# MAIN.net
KiCad netlist of a schematic drawn in Altium Designer
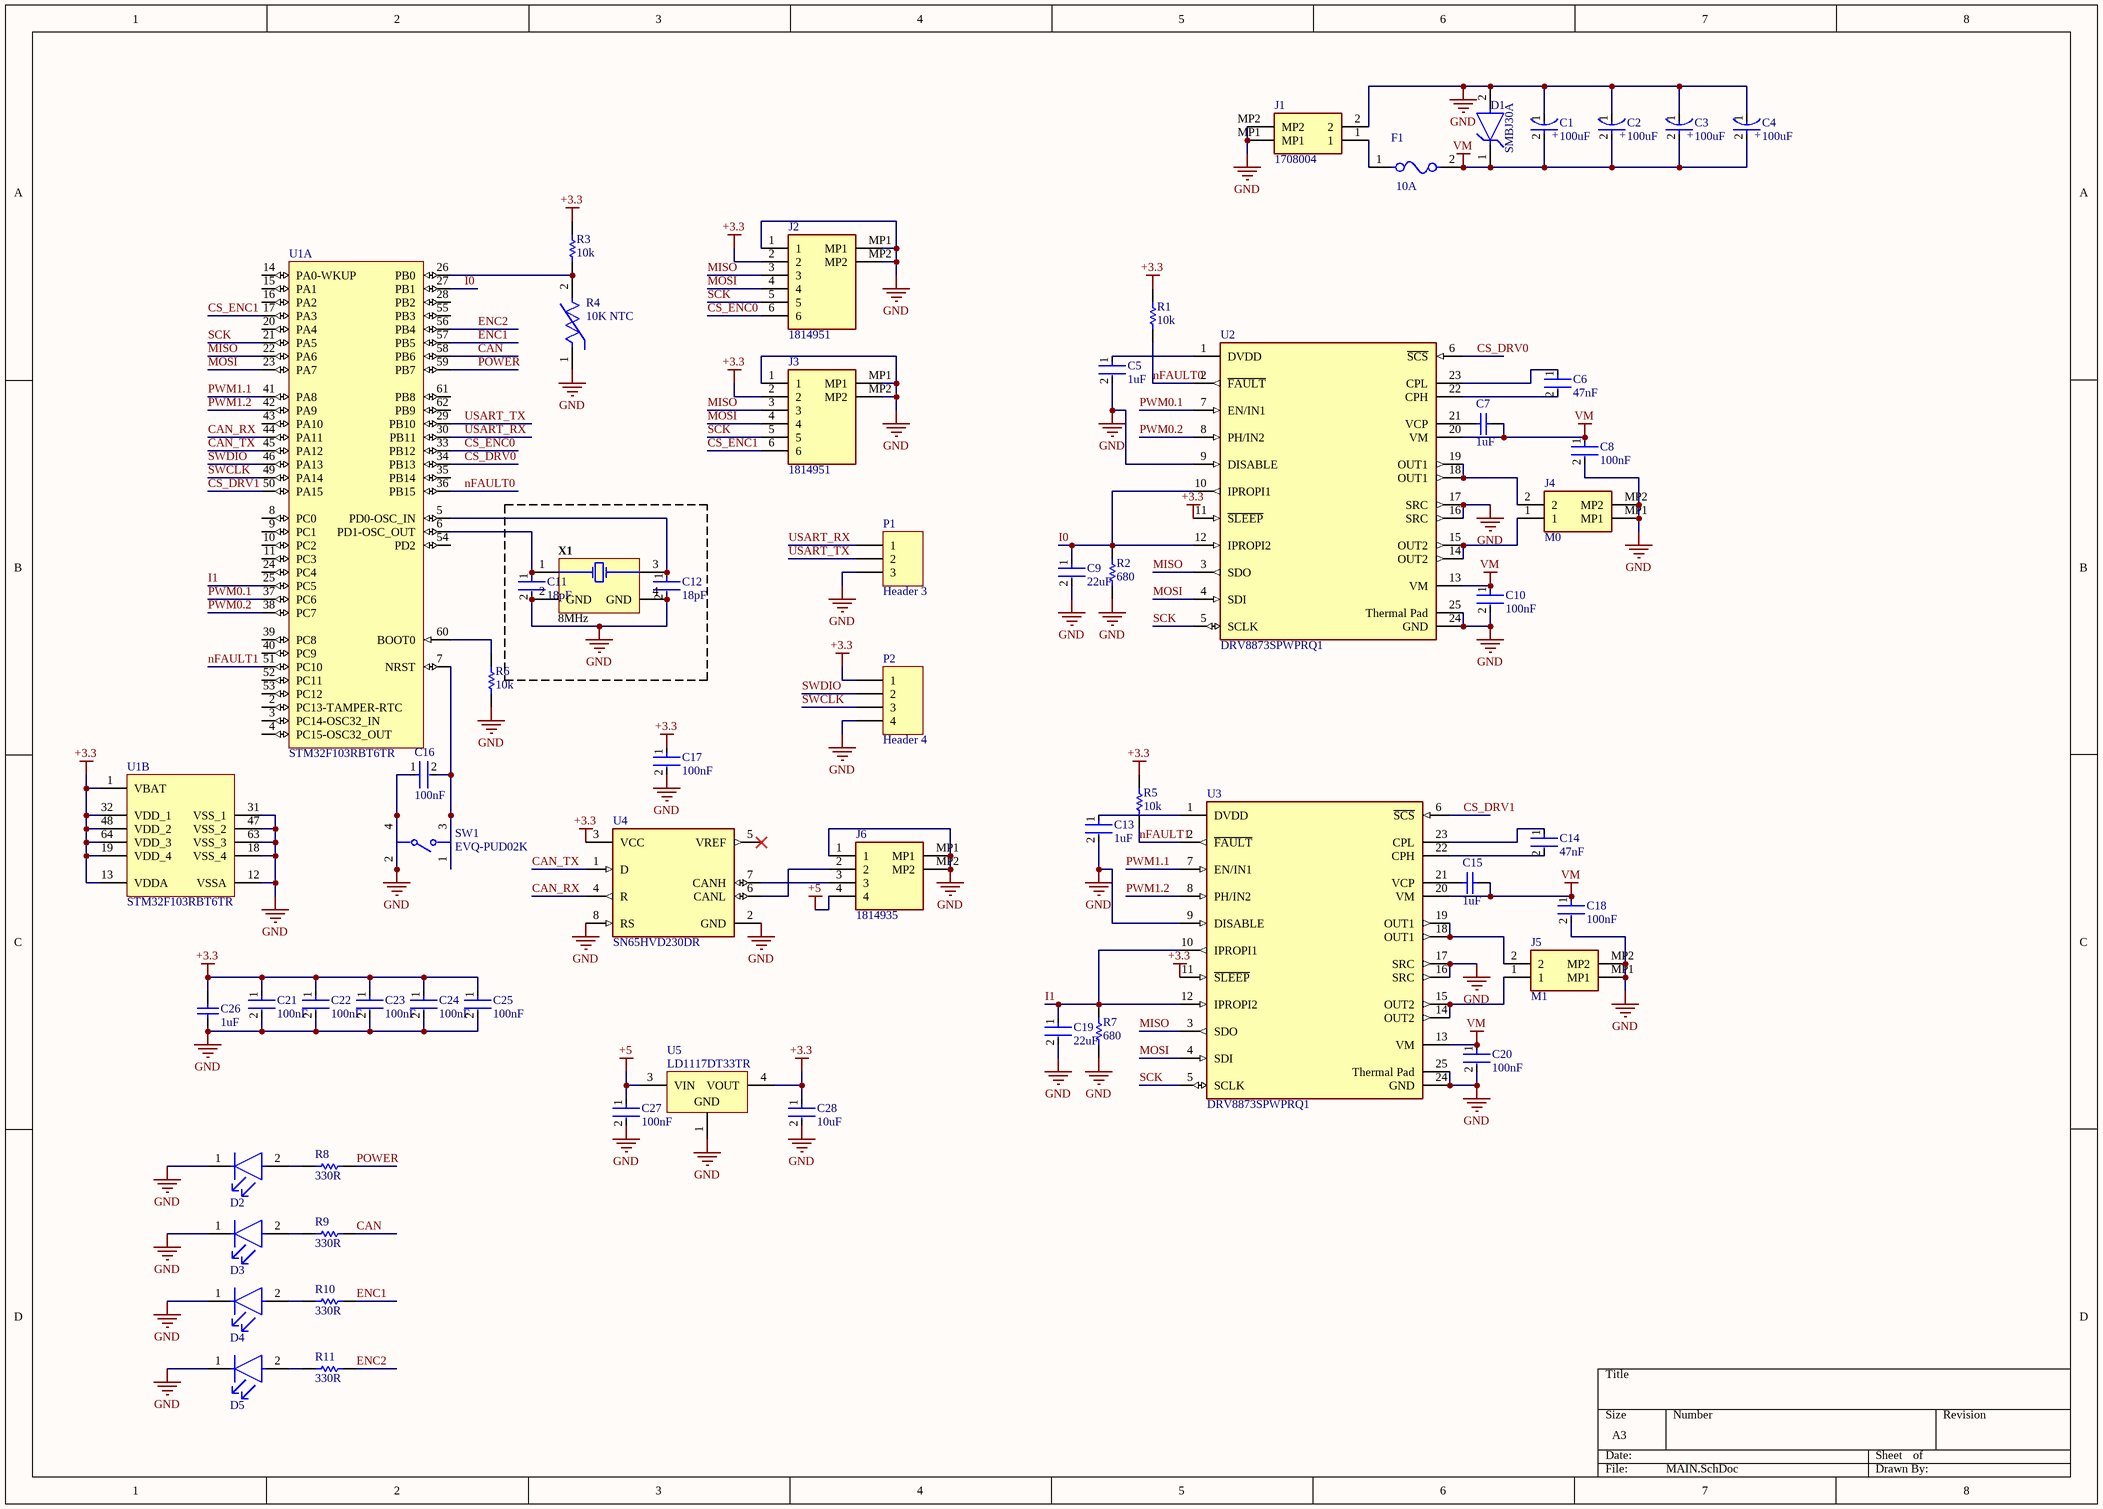
[diagram p0: MAIN.SchDoc]

(export (version "E")
  (design (tool "Eeschema 10.0.6"))
  (components
    (comp (ref "C1")
      (value "100uF")
      (footprint "FP-FTD-MFG")
      (description "CAP ALUM 100UF 20% 35V SMD")
      (fields (field (name "VOLTAGE") "35V") (field (name "TOLERANCE") "20%"))
      (libsource (lib "Altium Content Vault") (part "a00bbbee19879c290e62620ae7e47b1"))
    )
    (comp (ref "C2")
      (value "100uF")
      (footprint "FP-FTD-MFG")
      (description "CAP ALUM 100UF 20% 35V SMD")
      (fields (field (name "VOLTAGE") "35V") (field (name "TOLERANCE") "20%"))
      (libsource (lib "Altium Content Vault") (part "a00bbbee19879c290e62620ae7e47b1"))
    )
    (comp (ref "C3")
      (value "100uF")
      (footprint "FP-FTD-MFG")
      (description "CAP ALUM 100UF 20% 35V SMD")
      (fields (field (name "VOLTAGE") "35V") (field (name "TOLERANCE") "20%"))
      (libsource (lib "Altium Content Vault") (part "a00bbbee19879c290e62620ae7e47b1"))
    )
    (comp (ref "C4")
      (value "100uF")
      (footprint "FP-FTD-MFG")
      (description "CAP ALUM 100UF 20% 35V SMD")
      (fields (field (name "VOLTAGE") "35V") (field (name "TOLERANCE") "20%"))
      (libsource (lib "Altium Content Vault") (part "a00bbbee19879c290e62620ae7e47b1"))
    )
    (comp (ref "C5")
      (value "1uF")
      (footprint "FP-0805-L_2_01_0_2-W_1_25-IPC_B")
      (description "General Purpose Ceramic Capacitor, 0805, 100nF, 10%, X7R, 15%, 100V")
      (fields (field (name "VOLTAGE") "100V") (field (name "TOLERANCE") "10%"))
      (libsource (lib "Altium Content Vault") (part "b4654b650e69147ec39a6b967a45e02"))
    )
    (comp (ref "C6")
      (value "47nF")
      (footprint "FP-C0805C-DN-IPC_A")
      (description "CAP CER 0.047UF 50V X7R 0805")
      (fields
        (field (name "MANUFACTURER PART NUMBER") "C0805C473K5RACTU")
        (field (name "OCTOPART") "https://octopart.com/c0805c473k5ractu-kemet-138387")
      )
      (libsource (lib "Altium Content Vault") (part "b4654b650e69147ec39a6b967a45e02"))
    )
    (comp (ref "C7")
      (value "1uF")
      (footprint "CAPC2013X145X50ML20T25")
      (fields (field (name "MANUFACTURER") "Kemet") (field (name "PART NUMBER") "C0805C105K4PACTU"))
      (libsource (lib "Altium Content Vault") (part "CAP"))
    )
    (comp (ref "C8")
      (value "100nF")
      (footprint "FP-0805-L_2_01_0_2-W_1_25-MFG")
      (description "General Purpose Ceramic Capacitor, 0805, 100nF, 10%, X7R, 15%, 100V")
      (fields (field (name "VOLTAGE") "100V") (field (name "TOLERANCE") "10%"))
      (libsource (lib "Altium Content Vault") (part "b4654b650e69147ec39a6b967a45e02"))
    )
    (comp (ref "C9")
      (value "22uF")
      (footprint "FP-0805-L_2_01_0_2-W_1_25-IPC_B")
      (description "General Purpose Ceramic Capacitor, 0805, 100nF, 10%, X7R, 15%, 100V")
      (fields (field (name "VOLTAGE") "100V") (field (name "TOLERANCE") "10%"))
      (libsource (lib "Altium Content Vault") (part "b4654b650e69147ec39a6b967a45e02"))
    )
    (comp (ref "C10")
      (value "100nF")
      (footprint "FP-0805-L_2_01_0_2-W_1_25-MFG")
      (description "General Purpose Ceramic Capacitor, 0805, 100nF, 10%, X7R, 15%, 100V")
      (fields (field (name "VOLTAGE") "100V") (field (name "TOLERANCE") "10%"))
      (libsource (lib "Altium Content Vault") (part "b4654b650e69147ec39a6b967a45e02"))
    )
    (comp (ref "C11")
      (value "18pF")
      (footprint "FP-C0603C-CF-MFG")
      (description "CAP CER 18PF 100V 5% NP0 0603")
      (fields (field (name "TOLERANCE") "0.05") (field (name "MANUFACTURER") "KEMET"))
      (libsource (lib "Altium Content Vault") (part "b4654b650e69147ec39a6b967a45e02"))
    )
    (comp (ref "C12")
      (value "18pF")
      (footprint "FP-C0603C-CF-MFG")
      (description "CAP CER 18PF 100V 5% NP0 0603")
      (fields (field (name "TOLERANCE") "0.05") (field (name "MANUFACTURER") "KEMET"))
      (libsource (lib "Altium Content Vault") (part "b4654b650e69147ec39a6b967a45e02"))
    )
    (comp (ref "C13")
      (value "1uF")
      (footprint "FP-0805-L_2_01_0_2-W_1_25-IPC_B")
      (description "General Purpose Ceramic Capacitor, 0805, 100nF, 10%, X7R, 15%, 100V")
      (fields (field (name "VOLTAGE") "100V") (field (name "TOLERANCE") "10%"))
      (libsource (lib "Altium Content Vault") (part "b4654b650e69147ec39a6b967a45e02"))
    )
    (comp (ref "C14")
      (value "47nF")
      (footprint "FP-C0805C-DN-IPC_A")
      (description "CAP CER 0.047UF 50V X7R 0805")
      (fields
        (field (name "MANUFACTURER PART NUMBER") "C0805C473K5RACTU")
        (field (name "OCTOPART") "https://octopart.com/c0805c473k5ractu-kemet-138387")
      )
      (libsource (lib "Altium Content Vault") (part "b4654b650e69147ec39a6b967a45e02"))
    )
    (comp (ref "C15")
      (value "1uF")
      (footprint "CAPC2013X145X50ML20T25")
      (fields (field (name "MANUFACTURER") "Kemet") (field (name "PART NUMBER") "C0805C105K4PACTU"))
      (libsource (lib "Altium Content Vault") (part "CAP"))
    )
    (comp (ref "C16")
      (value "100nF")
      (footprint "FP-0805-L_2_01_0_2-W_1_25-IPC_B")
      (description "General Purpose Ceramic Capacitor, 0805, 100nF, 10%, X7R, 15%, 100V")
      (fields (field (name "VOLTAGE") "100V") (field (name "TOLERANCE") "10%"))
      (libsource (lib "Altium Content Vault") (part "b4654b650e69147ec39a6b967a45e02"))
    )
    (comp (ref "C17")
      (value "100nF")
      (footprint "FP-0805-L_2_01_0_2-W_1_25-MFG")
      (description "General Purpose Ceramic Capacitor, 0805, 100nF, 10%, X7R, 15%, 100V")
      (fields (field (name "VOLTAGE") "100V") (field (name "TOLERANCE") "10%"))
      (libsource (lib "Altium Content Vault") (part "b4654b650e69147ec39a6b967a45e02"))
    )
    (comp (ref "C18")
      (value "100nF")
      (footprint "FP-0805-L_2_01_0_2-W_1_25-MFG")
      (description "General Purpose Ceramic Capacitor, 0805, 100nF, 10%, X7R, 15%, 100V")
      (fields (field (name "VOLTAGE") "100V") (field (name "TOLERANCE") "10%"))
      (libsource (lib "Altium Content Vault") (part "b4654b650e69147ec39a6b967a45e02"))
    )
    (comp (ref "C19")
      (value "22uF")
      (footprint "FP-0805-L_2_01_0_2-W_1_25-IPC_B")
      (description "General Purpose Ceramic Capacitor, 0805, 100nF, 10%, X7R, 15%, 100V")
      (fields (field (name "VOLTAGE") "100V") (field (name "TOLERANCE") "10%"))
      (libsource (lib "Altium Content Vault") (part "b4654b650e69147ec39a6b967a45e02"))
    )
    (comp (ref "C20")
      (value "100nF")
      (footprint "FP-0805-L_2_01_0_2-W_1_25-MFG")
      (description "General Purpose Ceramic Capacitor, 0805, 100nF, 10%, X7R, 15%, 100V")
      (fields (field (name "VOLTAGE") "100V") (field (name "TOLERANCE") "10%"))
      (libsource (lib "Altium Content Vault") (part "b4654b650e69147ec39a6b967a45e02"))
    )
    (comp (ref "C21")
      (value "100nF")
      (footprint "FP-0805-L_2_01_0_2-W_1_25-IPC_B")
      (description "General Purpose Ceramic Capacitor, 0805, 100nF, 10%, X7R, 15%, 100V")
      (fields (field (name "VOLTAGE") "100V") (field (name "TOLERANCE") "10%"))
      (libsource (lib "Altium Content Vault") (part "b4654b650e69147ec39a6b967a45e02"))
    )
    (comp (ref "C22")
      (value "100nF")
      (footprint "FP-0805-L_2_01_0_2-W_1_25-IPC_B")
      (description "General Purpose Ceramic Capacitor, 0805, 100nF, 10%, X7R, 15%, 100V")
      (fields (field (name "VOLTAGE") "100V") (field (name "TOLERANCE") "10%"))
      (libsource (lib "Altium Content Vault") (part "b4654b650e69147ec39a6b967a45e02"))
    )
    (comp (ref "C23")
      (value "100nF")
      (footprint "FP-0805-L_2_01_0_2-W_1_25-IPC_B")
      (description "General Purpose Ceramic Capacitor, 0805, 100nF, 10%, X7R, 15%, 100V")
      (fields (field (name "VOLTAGE") "100V") (field (name "TOLERANCE") "10%"))
      (libsource (lib "Altium Content Vault") (part "b4654b650e69147ec39a6b967a45e02"))
    )
    (comp (ref "C24")
      (value "100nF")
      (footprint "FP-0805-L_2_01_0_2-W_1_25-IPC_B")
      (description "General Purpose Ceramic Capacitor, 0805, 100nF, 10%, X7R, 15%, 100V")
      (fields (field (name "VOLTAGE") "100V") (field (name "TOLERANCE") "10%"))
      (libsource (lib "Altium Content Vault") (part "b4654b650e69147ec39a6b967a45e02"))
    )
    (comp (ref "C25")
      (value "100nF")
      (footprint "FP-0805-L_2_01_0_2-W_1_25-IPC_B")
      (description "General Purpose Ceramic Capacitor, 0805, 100nF, 10%, X7R, 15%, 100V")
      (fields (field (name "VOLTAGE") "100V") (field (name "TOLERANCE") "10%"))
      (libsource (lib "Altium Content Vault") (part "b4654b650e69147ec39a6b967a45e02"))
    )
    (comp (ref "C26")
      (value "1uF")
      (footprint "CAPC2013X145X50ML20T25")
      (fields (field (name "MANUFACTURER") "Kemet") (field (name "PART NUMBER") "C0805C105K4PACTU"))
      (libsource (lib "Altium Content Vault") (part "CAP"))
    )
    (comp (ref "C27")
      (value "100nF")
      (footprint "FP-0805-L_2_01_0_2-W_1_25-IPC_B")
      (description "General Purpose Ceramic Capacitor, 0805, 100nF, 10%, X7R, 15%, 100V")
      (fields (field (name "VOLTAGE") "100V") (field (name "TOLERANCE") "10%"))
      (libsource (lib "Altium Content Vault") (part "b4654b650e69147ec39a6b967a45e02"))
    )
    (comp (ref "C28")
      (value "10uF")
      (footprint "FP-C0805C-DG-IPC_B")
      (description "CAP CER 10UF 10V X5R 0805")
      (fields (field (name "TOLERANCE") "10%") (field (name "MANUFACTURER PART NUMBER") "C0805C106K8PACTU"))
      (libsource (lib "Altium Content Vault") (part "11868f565c42a9108669ba33697ecf6"))
    )
    (comp (ref "D1")
      (value "SMBJ30A")
      (footprint "FP-SMBJ30A-E3-52-0")
      (description "TVS DIODE 30VWM 48.4VC DO214AA")
      (libsource (lib "Altium Content Vault") (part "d9da4cfb8af32e832502365dfa3d88e"))
    )
    (comp (ref "D2")
      (value "TLLG4401")
      (footprint "FP-6_544-5255_01-4-MFG")
      (description "TLLG4401 LED, Green, 2mcd, 3mmDia., T-1, +/-25deg, 565nm, 7mA, 1.9V Vf, 20V Vr, 20mW, -40")
      (libsource (lib "Altium Content Vault") (part "8706943c75ba83719d021d2fdc84c58"))
    )
    (comp (ref "D3")
      (value "TLLG4401")
      (footprint "FP-6_544-5255_01-4-MFG")
      (description "TLLG4401 LED, Green, 2mcd, 3mmDia., T-1, +/-25deg, 565nm, 7mA, 1.9V Vf, 20V Vr, 20mW, -40")
      (libsource (lib "Altium Content Vault") (part "8706943c75ba83719d021d2fdc84c58"))
    )
    (comp (ref "D4")
      (value "TLLG4401")
      (footprint "FP-6_544-5255_01-4-MFG")
      (description "TLLG4401 LED, Green, 2mcd, 3mmDia., T-1, +/-25deg, 565nm, 7mA, 1.9V Vf, 20V Vr, 20mW, -40")
      (libsource (lib "Altium Content Vault") (part "8706943c75ba83719d021d2fdc84c58"))
    )
    (comp (ref "D5")
      (value "TLLG4401")
      (footprint "FP-6_544-5255_01-4-MFG")
      (description "TLLG4401 LED, Green, 2mcd, 3mmDia., T-1, +/-25deg, 565nm, 7mA, 1.9V Vf, 20V Vr, 20mW, -40")
      (libsource (lib "Altium Content Vault") (part "8706943c75ba83719d021d2fdc84c58"))
    )
    (comp (ref "F1")
      (value "10A")
      (footprint "FP-0154-MFG")
      (description "FUSE BRD MNT 4A 125VAC/VDC 2SMD")
      (fields
        (field (name "MANUFACTURER PART NUMBER") "0154004.DR")
        (field (name "MANUFACTURER") "Littelfuse")
      )
      (libsource (lib "Altium Content Vault") (part "5bcf9b9f640e542cf0359d10258e979"))
    )
    (comp (ref "J1")
      (value "1708004")
      (footprint "1708004")
      (description "Pluggable Terminal Blocks PTSM 0,5/ 2-HH- 2,5-SMD WH R32")
      (fields (field (name "MOUSER PART NUMBER") "651-1708004"))
      (libsource (lib "1708004") (part "1708004"))
    )
    (comp (ref "J2")
      (value "1814951")
      (footprint "1814951")
      (description "Pluggable Terminal Blocks PTSM 0,5/ 6-HH0-2,5- SMD WH R44")
      (libsource (lib "1814951") (part "1814951"))
    )
    (comp (ref "J3")
      (value "1814951")
      (footprint "1814951")
      (description "Pluggable Terminal Blocks PTSM 0,5/ 6-HH0-2,5- SMD WH R44")
      (libsource (lib "1814951") (part "1814951"))
    )
    (comp (ref "J4")
      (value "M0")
      (footprint "1815125")
      (description "Phoenix Contact PTSM Series, 2.5mm Pitch Printed Circuit Board Connector, 6A")
      (fields
        (field (name "MOUSER PART NUMBER") "651-1815125")
        (field (name "MANUFACTURER_PART_NUMBER") "1815125")
      )
      (libsource (lib "1815125") (part "1815125"))
    )
    (comp (ref "J5")
      (value "M1")
      (footprint "1815125")
      (description "Phoenix Contact PTSM Series, 2.5mm Pitch Printed Circuit Board Connector, 6A")
      (fields
        (field (name "MOUSER PART NUMBER") "651-1815125")
        (field (name "MANUFACTURER_PART_NUMBER") "1815125")
      )
      (libsource (lib "1815125") (part "1815125"))
    )
    (comp (ref "J6")
      (value "1814935")
      (footprint "1814935")
      (description "Pluggable Terminal Blocks PTSM 0,5/ 4-HH0-2,5- SMD WH R32")
      (libsource (lib "1814935") (part "1814935"))
    )
    (comp (ref "P1")
      (value "Header 3")
      (footprint "HDR1X3")
      (description "Header, 3-Pin")
      (fields (field (name "PUBLISHER") "Altium Limited"))
      (libsource (lib "Miscellaneous Connectors") (part "Header 3"))
    )
    (comp (ref "P2")
      (value "Header 4")
      (footprint "HDR1X4")
      (description "Header, 4-Pin")
      (fields (field (name "PUBLISHER") "Altium Limited"))
      (libsource (lib "Miscellaneous Connectors") (part "Header 4"))
    )
    (comp (ref "R1")
      (value "10k")
      (footprint "RESC2013X60X35NL10T20")
      (description "Chip Resistor, 10 KOhm, +/- 1%, 0.125 W, -55 to 155 degC, 0805 (2012 Metric), RoHS, Tape and Reel")
      (fields (field (name "MANUFACTURER") "Yageo"))
      (libsource (lib "Altium Content Vault") (part "RES-2"))
    )
    (comp (ref "R2")
      (value "680")
      (footprint "RESC2013X60X35NL10T20")
      (description "Chip Resistor, 10 KOhm, +/- 1%, 0.125 W, -55 to 155 degC, 0805 (2012 Metric), RoHS, Tape and Reel")
      (fields (field (name "MANUFACTURER") "Yageo"))
      (libsource (lib "Altium Content Vault") (part "RES-2"))
    )
    (comp (ref "R3")
      (value "10k")
      (footprint "RESC2013X60X35ML10T20")
      (fields (field (name "TOLERANCE") "5%") (field (name "MANUFACTURER") "Yageo"))
      (libsource (lib "Altium Content Vault") (part "RES-2"))
    )
    (comp (ref "R4")
      (value "10K NTC")
      (footprint "FP-NCP18-0_15-IPC_A")
      (description "NTC Thermistor for Temperature Sensor, 0603, 10kΩ, 1%, 0.1mA, 5V")
      (fields (field (name "TOLERANCE") "1%"))
      (libsource (lib "Altium Content Vault") (part "3b148a6ebabc5fb4d708a66c052d352"))
    )
    (comp (ref "R5")
      (value "10k")
      (footprint "RESC2013X60X35NL10T20")
      (description "Chip Resistor, 10 KOhm, +/- 1%, 0.125 W, -55 to 155 degC, 0805 (2012 Metric), RoHS, Tape and Reel")
      (fields (field (name "MANUFACTURER") "Yageo"))
      (libsource (lib "Altium Content Vault") (part "RES-2"))
    )
    (comp (ref "R6")
      (value "10k")
      (footprint "RESC2013X60X35ML10T20")
      (fields (field (name "TOLERANCE") "5%") (field (name "MANUFACTURER") "Yageo"))
      (libsource (lib "Altium Content Vault") (part "RES-2"))
    )
    (comp (ref "R7")
      (value "680")
      (footprint "RESC2013X60X35NL10T20")
      (description "Chip Resistor, 10 KOhm, +/- 1%, 0.125 W, -55 to 155 degC, 0805 (2012 Metric), RoHS, Tape and Reel")
      (fields (field (name "MANUFACTURER") "Yageo"))
      (libsource (lib "Altium Content Vault") (part "RES-2"))
    )
    (comp (ref "R8")
      (value "330R")
      (footprint "RESC2013X60X35ML10T20")
      (description "Chip Resistor, 1 KOhm, +/- 1%, 125 mW, -55 to 155 degC, 0805 (2012 Metric), RoHS, Tape and Reel")
      (fields (field (name "TOLERANCE") "1%") (field (name "MANUFACTURER") "Yageo"))
      (libsource (lib "Altium Content Vault") (part "RES-2"))
    )
    (comp (ref "R9")
      (value "330R")
      (footprint "RESC2013X60X35ML10T20")
      (description "Chip Resistor, 1 KOhm, +/- 1%, 125 mW, -55 to 155 degC, 0805 (2012 Metric), RoHS, Tape and Reel")
      (fields (field (name "TOLERANCE") "1%") (field (name "MANUFACTURER") "Yageo"))
      (libsource (lib "Altium Content Vault") (part "RES-2"))
    )
    (comp (ref "R10")
      (value "330R")
      (footprint "RESC2013X60X35ML10T20")
      (description "Chip Resistor, 1 KOhm, +/- 1%, 125 mW, -55 to 155 degC, 0805 (2012 Metric), RoHS, Tape and Reel")
      (fields (field (name "TOLERANCE") "1%") (field (name "MANUFACTURER") "Yageo"))
      (libsource (lib "Altium Content Vault") (part "RES-2"))
    )
    (comp (ref "R11")
      (value "330R")
      (footprint "RESC2013X60X35ML10T20")
      (description "Chip Resistor, 1 KOhm, +/- 1%, 125 mW, -55 to 155 degC, 0805 (2012 Metric), RoHS, Tape and Reel")
      (fields (field (name "TOLERANCE") "1%") (field (name "MANUFACTURER") "Yageo"))
      (libsource (lib "Altium Content Vault") (part "RES-2"))
    )
    (comp (ref "SW1")
      (value "EVQ-PUD02K")
      (footprint "FP-EVQ-PUD02K-MFG")
      (description "SWITCH TACTILE SPST-NO 0.05A 12V")
      (libsource (lib "Altium Content Vault") (part "98412ef6bd26695bde79fccaf8fa8e7"))
    )
    (comp (ref "U1")
      (value "STM32F103RBT6TR")
      (footprint "STM-LQFP64_V")
      (libsource (lib "Altium Content Vault") (part "MC-ARM-STM32F103X8_B-SQ64"))
    )
    (comp (ref "U2")
      (value "DRV8873SPWPRQ1")
      (footprint "FP-PWP0024J-MFG")
      (description "IC MTRDRV UNIPLR 0-5.5V 24HTSSOP")
      (libsource (lib "Altium Content Vault") (part "639cfc0396780f9562c68c0b1c9b09f"))
    )
    (comp (ref "U3")
      (value "DRV8873SPWPRQ1")
      (footprint "FP-PWP0024J-MFG")
      (description "IC MTRDRV UNIPLR 0-5.5V 24HTSSOP")
      (libsource (lib "Altium Content Vault") (part "639cfc0396780f9562c68c0b1c9b09f"))
    )
    (comp (ref "U4")
      (value "SN65HVD230DR")
      (footprint "FP-D0008A-IPC_A")
      (description "IC TRANSCEIVER HALF 1/1 8SOIC")
      (libsource (lib "Altium Content Vault") (part "43b56812b1adf0e60a7acfb7c27ab91"))
    )
    (comp (ref "U5")
      (value "LD1117DT33TR")
      (footprint "TO-252_M")
      (description "Fixed Low Drop Positive Voltage Regulator, 3.3V, 3-Pin DPAK, Tape and Reel")
      (libsource (lib "Altium Content Vault") (part "PM-REG-LD1117-SOT3"))
    )
    (comp (ref "X1")
      (value "8MHz")
      (footprint "TXC-7B-4_V")
      (description "SMD Seam Sealing Crystal, 8 MHz, +/- 30 ppm, 18 pF, -10 to 70 degC, 4-Pin SMD, RoHS, Tape and Reel")
      (fields (field (name "TOLERANCE") "1%"))
      (libsource (lib "Altium Content Vault") (part "XTAL-1-3-4"))
    )
  )
  (nets
    (net (code "1") (name "+3.3") (class "Default")
      (node (ref "C17") (pin "1") (pinfunction "1_1") (pintype "passive"))
      (node (ref "C21") (pin "1") (pinfunction "1_1") (pintype "passive"))
      (node (ref "C22") (pin "1") (pinfunction "1_1") (pintype "passive"))
      (node (ref "C23") (pin "1") (pinfunction "1_1") (pintype "passive"))
      (node (ref "C24") (pin "1") (pinfunction "1_1") (pintype "passive"))
      (node (ref "C25") (pin "1") (pinfunction "1_1") (pintype "passive"))
      (node (ref "C26") (pin "2") (pinfunction "2_2") (pintype "passive"))
      (node (ref "C28") (pin "1") (pinfunction "1_1") (pintype "passive"))
      (node (ref "J2") (pin "2") (pinfunction "2_2") (pintype "passive"))
      (node (ref "J3") (pin "2") (pinfunction "2_2") (pintype "passive"))
      (node (ref "P2") (pin "1") (pinfunction "1_1") (pintype "passive"))
      (node (ref "R1") (pin "2") (pinfunction "2_2") (pintype "passive"))
      (node (ref "R3") (pin "2") (pinfunction "2_2") (pintype "passive"))
      (node (ref "R5") (pin "2") (pinfunction "2_2") (pintype "passive"))
      (node (ref "U1") (pin "1") (pinfunction "VBAT_1") (pintype "power_in"))
      (node (ref "U1") (pin "13") (pinfunction "VDDA_13") (pintype "power_in"))
      (node (ref "U1") (pin "19") (pinfunction "VDD_4_19") (pintype "power_in"))
      (node (ref "U1") (pin "32") (pinfunction "VDD_1_32") (pintype "power_in"))
      (node (ref "U1") (pin "48") (pinfunction "VDD_2_48") (pintype "power_in"))
      (node (ref "U1") (pin "64") (pinfunction "VDD_3_64") (pintype "power_in"))
      (node (ref "U2") (pin "11") (pinfunction "~{SLEEP}_11") (pintype "input"))
      (node (ref "U3") (pin "11") (pinfunction "~{SLEEP}_11") (pintype "input"))
      (node (ref "U4") (pin "3") (pinfunction "VCC_3") (pintype "power_in"))
      (node (ref "U5") (pin "4") (pinfunction "VOUT_4") (pintype "power_in"))
    )
    (net (code "2") (name "+5") (class "Default")
      (node (ref "C27") (pin "1") (pinfunction "1_1") (pintype "passive"))
      (node (ref "J6") (pin "4") (pinfunction "4_4") (pintype "passive"))
      (node (ref "U5") (pin "3") (pinfunction "VIN_3") (pintype "power_in"))
    )
    (net (code "3") (name "/CAN") (class "Default")
      (node (ref "R9") (pin "1") (pinfunction "1_1") (pintype "passive"))
      (node (ref "U1") (pin "58") (pinfunction "PB6_58") (pintype "bidirectional"))
    )
    (net (code "4") (name "/CAN_RX") (class "Default")
      (node (ref "U1") (pin "44") (pinfunction "PA11_44") (pintype "bidirectional"))
      (node (ref "U4") (pin "4") (pinfunction "R_4") (pintype "output"))
    )
    (net (code "5") (name "/CAN_TX") (class "Default")
      (node (ref "U1") (pin "45") (pinfunction "PA12_45") (pintype "bidirectional"))
      (node (ref "U4") (pin "1") (pinfunction "D_1") (pintype "input"))
    )
    (net (code "6") (name "/CS_DRV0") (class "Default")
      (node (ref "U1") (pin "34") (pinfunction "PB13_34") (pintype "bidirectional"))
      (node (ref "U2") (pin "6") (pinfunction "~{SCS}_6") (pintype "input"))
    )
    (net (code "7") (name "/CS_DRV1") (class "Default")
      (node (ref "U1") (pin "50") (pinfunction "PA15_50") (pintype "bidirectional"))
      (node (ref "U3") (pin "6") (pinfunction "~{SCS}_6") (pintype "input"))
    )
    (net (code "8") (name "/CS_ENC0") (class "Default")
      (node (ref "J2") (pin "6") (pinfunction "6_6") (pintype "passive"))
      (node (ref "U1") (pin "33") (pinfunction "PB12_33") (pintype "bidirectional"))
    )
    (net (code "9") (name "/CS_ENC1") (class "Default")
      (node (ref "J3") (pin "6") (pinfunction "6_6") (pintype "passive"))
      (node (ref "U1") (pin "17") (pinfunction "PA3_17") (pintype "bidirectional"))
    )
    (net (code "10") (name "/ENC1") (class "Default")
      (node (ref "R10") (pin "1") (pinfunction "1_1") (pintype "passive"))
      (node (ref "U1") (pin "57") (pinfunction "PB5_57") (pintype "bidirectional"))
    )
    (net (code "11") (name "/ENC2") (class "Default")
      (node (ref "R11") (pin "1") (pinfunction "1_1") (pintype "passive"))
      (node (ref "U1") (pin "56") (pinfunction "PB4_56") (pintype "bidirectional"))
    )
    (net (code "12") (name "/I0") (class "Default")
      (node (ref "C9") (pin "1") (pinfunction "1_1") (pintype "passive"))
      (node (ref "R2") (pin "2") (pinfunction "2_2") (pintype "passive"))
      (node (ref "U1") (pin "27") (pinfunction "PB1_27") (pintype "bidirectional"))
      (node (ref "U2") (pin "10") (pinfunction "IPROPI1_10") (pintype "output"))
      (node (ref "U2") (pin "12") (pinfunction "IPROPI2_12") (pintype "input"))
    )
    (net (code "13") (name "/I1") (class "Default")
      (node (ref "C19") (pin "1") (pinfunction "1_1") (pintype "passive"))
      (node (ref "R7") (pin "2") (pinfunction "2_2") (pintype "passive"))
      (node (ref "U1") (pin "25") (pinfunction "PC5_25") (pintype "bidirectional"))
      (node (ref "U3") (pin "10") (pinfunction "IPROPI1_10") (pintype "output"))
      (node (ref "U3") (pin "12") (pinfunction "IPROPI2_12") (pintype "input"))
    )
    (net (code "14") (name "/MISO") (class "Default")
      (node (ref "J2") (pin "3") (pinfunction "3_3") (pintype "passive"))
      (node (ref "J3") (pin "3") (pinfunction "3_3") (pintype "passive"))
      (node (ref "U1") (pin "22") (pinfunction "PA6_22") (pintype "bidirectional"))
      (node (ref "U2") (pin "3") (pinfunction "SDO_3") (pintype "output"))
      (node (ref "U3") (pin "3") (pinfunction "SDO_3") (pintype "output"))
    )
    (net (code "15") (name "/MOSI") (class "Default")
      (node (ref "J2") (pin "4") (pinfunction "4_4") (pintype "passive"))
      (node (ref "J3") (pin "4") (pinfunction "4_4") (pintype "passive"))
      (node (ref "U1") (pin "23") (pinfunction "PA7_23") (pintype "bidirectional"))
      (node (ref "U2") (pin "4") (pinfunction "SDI_4") (pintype "input"))
      (node (ref "U3") (pin "4") (pinfunction "SDI_4") (pintype "input"))
    )
    (net (code "16") (name "/POWER") (class "Default")
      (node (ref "R8") (pin "1") (pinfunction "1_1") (pintype "passive"))
      (node (ref "U1") (pin "59") (pinfunction "PB7_59") (pintype "bidirectional"))
    )
    (net (code "17") (name "/PWM0.1") (class "Default")
      (node (ref "U1") (pin "37") (pinfunction "PC6_37") (pintype "bidirectional"))
      (node (ref "U2") (pin "7") (pinfunction "EN/IN1_7") (pintype "input"))
    )
    (net (code "18") (name "/PWM0.2") (class "Default")
      (node (ref "U1") (pin "38") (pinfunction "PC7_38") (pintype "bidirectional"))
      (node (ref "U2") (pin "8") (pinfunction "PH/IN2_8") (pintype "input"))
    )
    (net (code "19") (name "/PWM1.1") (class "Default")
      (node (ref "U1") (pin "41") (pinfunction "PA8_41") (pintype "bidirectional"))
      (node (ref "U3") (pin "7") (pinfunction "EN/IN1_7") (pintype "input"))
    )
    (net (code "20") (name "/PWM1.2") (class "Default")
      (node (ref "U1") (pin "42") (pinfunction "PA9_42") (pintype "bidirectional"))
      (node (ref "U3") (pin "8") (pinfunction "PH/IN2_8") (pintype "input"))
    )
    (net (code "21") (name "/SCK") (class "Default")
      (node (ref "J2") (pin "5") (pinfunction "5_5") (pintype "passive"))
      (node (ref "J3") (pin "5") (pinfunction "5_5") (pintype "passive"))
      (node (ref "U1") (pin "21") (pinfunction "PA5_21") (pintype "bidirectional"))
      (node (ref "U2") (pin "5") (pinfunction "SCLK_5") (pintype "bidirectional"))
      (node (ref "U3") (pin "5") (pinfunction "SCLK_5") (pintype "bidirectional"))
    )
    (net (code "22") (name "/SWCLK") (class "Default")
      (node (ref "P2") (pin "3") (pinfunction "3_3") (pintype "passive"))
      (node (ref "U1") (pin "49") (pinfunction "PA14_49") (pintype "bidirectional"))
    )
    (net (code "23") (name "/SWDIO") (class "Default")
      (node (ref "P2") (pin "2") (pinfunction "2_2") (pintype "passive"))
      (node (ref "U1") (pin "46") (pinfunction "PA13_46") (pintype "bidirectional"))
    )
    (net (code "24") (name "/USART_RX") (class "Default")
      (node (ref "P1") (pin "1") (pinfunction "1_1") (pintype "passive"))
      (node (ref "U1") (pin "30") (pinfunction "PB11_30") (pintype "bidirectional"))
    )
    (net (code "25") (name "/USART_TX") (class "Default")
      (node (ref "P1") (pin "2") (pinfunction "2_2") (pintype "passive"))
      (node (ref "U1") (pin "29") (pinfunction "PB10_29") (pintype "bidirectional"))
    )
    (net (code "26") (name "/nFAULT0") (class "Default")
      (node (ref "R1") (pin "1") (pinfunction "1_1") (pintype "passive"))
      (node (ref "U1") (pin "36") (pinfunction "PB15_36") (pintype "bidirectional"))
      (node (ref "U2") (pin "2") (pinfunction "~{FAULT}_2") (pintype "output"))
    )
    (net (code "27") (name "/nFAULT1") (class "Default")
      (node (ref "R5") (pin "1") (pinfunction "1_1") (pintype "passive"))
      (node (ref "U1") (pin "51") (pinfunction "PC10_51") (pintype "bidirectional"))
      (node (ref "U3") (pin "2") (pinfunction "~{FAULT}_2") (pintype "output"))
    )
    (net (code "28") (name "GND") (class "Default")
      (node (ref "C1") (pin "1") (pinfunction "C_1") (pintype "passive"))
      (node (ref "C10") (pin "2") (pinfunction "2_2") (pintype "passive"))
      (node (ref "C11") (pin "2") (pinfunction "2_2") (pintype "passive"))
      (node (ref "C12") (pin "2") (pinfunction "2_2") (pintype "passive"))
      (node (ref "C13") (pin "2") (pinfunction "2_2") (pintype "passive"))
      (node (ref "C16") (pin "1") (pinfunction "1_1") (pintype "passive"))
      (node (ref "C17") (pin "2") (pinfunction "2_2") (pintype "passive"))
      (node (ref "C18") (pin "2") (pinfunction "2_2") (pintype "passive"))
      (node (ref "C19") (pin "2") (pinfunction "2_2") (pintype "passive"))
      (node (ref "C2") (pin "1") (pinfunction "C_1") (pintype "passive"))
      (node (ref "C20") (pin "2") (pinfunction "2_2") (pintype "passive"))
      (node (ref "C21") (pin "2") (pinfunction "2_2") (pintype "passive"))
      (node (ref "C22") (pin "2") (pinfunction "2_2") (pintype "passive"))
      (node (ref "C23") (pin "2") (pinfunction "2_2") (pintype "passive"))
      (node (ref "C24") (pin "2") (pinfunction "2_2") (pintype "passive"))
      (node (ref "C25") (pin "2") (pinfunction "2_2") (pintype "passive"))
      (node (ref "C26") (pin "1") (pinfunction "1_1") (pintype "passive"))
      (node (ref "C27") (pin "2") (pinfunction "2_2") (pintype "passive"))
      (node (ref "C28") (pin "2") (pinfunction "2_2") (pintype "passive"))
      (node (ref "C3") (pin "1") (pinfunction "C_1") (pintype "passive"))
      (node (ref "C4") (pin "1") (pinfunction "C_1") (pintype "passive"))
      (node (ref "C5") (pin "2") (pinfunction "2_2") (pintype "passive"))
      (node (ref "C8") (pin "2") (pinfunction "2_2") (pintype "passive"))
      (node (ref "C9") (pin "2") (pinfunction "2_2") (pintype "passive"))
      (node (ref "D1") (pin "2") (pinfunction "A_2") (pintype "passive"))
      (node (ref "D2") (pin "1") (pinfunction "C_1") (pintype "passive"))
      (node (ref "D3") (pin "1") (pinfunction "C_1") (pintype "passive"))
      (node (ref "D4") (pin "1") (pinfunction "C_1") (pintype "passive"))
      (node (ref "D5") (pin "1") (pinfunction "C_1") (pintype "passive"))
      (node (ref "J1") (pin "2") (pinfunction "2_2") (pintype "passive"))
      (node (ref "J1") (pin "MP1") (pinfunction "MP1_MP1") (pintype "passive"))
      (node (ref "J1") (pin "MP2") (pinfunction "MP2_MP2") (pintype "passive"))
      (node (ref "J2") (pin "1") (pinfunction "1_1") (pintype "passive"))
      (node (ref "J2") (pin "MP1") (pinfunction "MP1_MP1") (pintype "passive"))
      (node (ref "J2") (pin "MP2") (pinfunction "MP2_MP2") (pintype "passive"))
      (node (ref "J3") (pin "1") (pinfunction "1_1") (pintype "passive"))
      (node (ref "J3") (pin "MP1") (pinfunction "MP1_MP1") (pintype "passive"))
      (node (ref "J3") (pin "MP2") (pinfunction "MP2_MP2") (pintype "passive"))
      (node (ref "J4") (pin "MP1") (pinfunction "MP1_MP1") (pintype "passive"))
      (node (ref "J4") (pin "MP2") (pinfunction "MP2_MP2") (pintype "passive"))
      (node (ref "J5") (pin "MP1") (pinfunction "MP1_MP1") (pintype "passive"))
      (node (ref "J5") (pin "MP2") (pinfunction "MP2_MP2") (pintype "passive"))
      (node (ref "J6") (pin "1") (pinfunction "1_1") (pintype "passive"))
      (node (ref "J6") (pin "MP1") (pinfunction "MP1_MP1") (pintype "passive"))
      (node (ref "J6") (pin "MP2") (pinfunction "MP2_MP2") (pintype "passive"))
      (node (ref "P1") (pin "3") (pinfunction "3_3") (pintype "passive"))
      (node (ref "P2") (pin "4") (pinfunction "4_4") (pintype "passive"))
      (node (ref "R2") (pin "1") (pinfunction "1_1") (pintype "passive"))
      (node (ref "R4") (pin "1") (pinfunction "1_1") (pintype "passive"))
      (node (ref "R6") (pin "1") (pinfunction "1_1") (pintype "passive"))
      (node (ref "R7") (pin "1") (pinfunction "1_1") (pintype "passive"))
      (node (ref "SW1") (pin "2") (pinfunction "2_2") (pintype "passive"))
      (node (ref "SW1") (pin "4") (pinfunction "4_4") (pintype "passive"))
      (node (ref "U1") (pin "12") (pinfunction "VSSA_12") (pintype "power_in"))
      (node (ref "U1") (pin "18") (pinfunction "VSS_4_18") (pintype "power_in"))
      (node (ref "U1") (pin "31") (pinfunction "VSS_1_31") (pintype "power_in"))
      (node (ref "U1") (pin "47") (pinfunction "VSS_2_47") (pintype "power_in"))
      (node (ref "U1") (pin "63") (pinfunction "VSS_3_63") (pintype "power_in"))
      (node (ref "U2") (pin "16") (pinfunction "SRC_16") (pintype "output"))
      (node (ref "U2") (pin "17") (pinfunction "SRC_17") (pintype "output"))
      (node (ref "U2") (pin "24") (pinfunction "GND_24") (pintype "power_in"))
      (node (ref "U2") (pin "25") (pinfunction "Thermal_Pad_25") (pintype "power_in"))
      (node (ref "U2") (pin "9") (pinfunction "DISABLE_9") (pintype "input"))
      (node (ref "U3") (pin "16") (pinfunction "SRC_16") (pintype "output"))
      (node (ref "U3") (pin "17") (pinfunction "SRC_17") (pintype "output"))
      (node (ref "U3") (pin "24") (pinfunction "GND_24") (pintype "power_in"))
      (node (ref "U3") (pin "25") (pinfunction "Thermal_Pad_25") (pintype "power_in"))
      (node (ref "U3") (pin "9") (pinfunction "DISABLE_9") (pintype "input"))
      (node (ref "U4") (pin "2") (pinfunction "GND_2") (pintype "power_in"))
      (node (ref "U4") (pin "8") (pinfunction "RS_8") (pintype "input"))
      (node (ref "U5") (pin "1") (pinfunction "GND_1") (pintype "power_in"))
      (node (ref "X1") (pin "2") (pinfunction "GND_2") (pintype "power_in"))
      (node (ref "X1") (pin "4") (pinfunction "GND_4") (pintype "power_in"))
    )
    (net (code "29") (name "Net-(D2-A)") (class "Default")
      (node (ref "D2") (pin "2") (pinfunction "A_2") (pintype "passive"))
      (node (ref "R8") (pin "2") (pinfunction "2_2") (pintype "passive"))
    )
    (net (code "30") (name "Net-(D3-A)") (class "Default")
      (node (ref "D3") (pin "2") (pinfunction "A_2") (pintype "passive"))
      (node (ref "R9") (pin "2") (pinfunction "2_2") (pintype "passive"))
    )
    (net (code "31") (name "Net-(D4-A)") (class "Default")
      (node (ref "D4") (pin "2") (pinfunction "A_2") (pintype "passive"))
      (node (ref "R10") (pin "2") (pinfunction "2_2") (pintype "passive"))
    )
    (net (code "32") (name "Net-(D5-A)") (class "Default")
      (node (ref "D5") (pin "2") (pinfunction "A_2") (pintype "passive"))
      (node (ref "R11") (pin "2") (pinfunction "2_2") (pintype "passive"))
    )
    (net (code "33") (name "Net-(F1-Pad1)") (class "Default")
      (node (ref "F1") (pin "1") (pinfunction "1_1") (pintype "passive"))
      (node (ref "J1") (pin "1") (pinfunction "1_1") (pintype "passive"))
    )
    (net (code "34") (name "Net-(J4-Pad1)") (class "Default")
      (node (ref "J4") (pin "1") (pinfunction "1_1") (pintype "passive"))
      (node (ref "U2") (pin "14") (pinfunction "OUT2_14") (pintype "output"))
      (node (ref "U2") (pin "15") (pinfunction "OUT2_15") (pintype "output"))
    )
    (net (code "35") (name "Net-(J4-Pad2)") (class "Default")
      (node (ref "J4") (pin "2") (pinfunction "2_2") (pintype "passive"))
      (node (ref "U2") (pin "18") (pinfunction "OUT1_18") (pintype "output"))
      (node (ref "U2") (pin "19") (pinfunction "OUT1_19") (pintype "output"))
    )
    (net (code "36") (name "Net-(J5-Pad1)") (class "Default")
      (node (ref "J5") (pin "1") (pinfunction "1_1") (pintype "passive"))
      (node (ref "U3") (pin "14") (pinfunction "OUT2_14") (pintype "output"))
      (node (ref "U3") (pin "15") (pinfunction "OUT2_15") (pintype "output"))
    )
    (net (code "37") (name "Net-(J5-Pad2)") (class "Default")
      (node (ref "J5") (pin "2") (pinfunction "2_2") (pintype "passive"))
      (node (ref "U3") (pin "18") (pinfunction "OUT1_18") (pintype "output"))
      (node (ref "U3") (pin "19") (pinfunction "OUT1_19") (pintype "output"))
    )
    (net (code "38") (name "Net-(U1A-BOOT0)") (class "Default")
      (node (ref "R6") (pin "2") (pinfunction "2_2") (pintype "passive"))
      (node (ref "U1") (pin "60") (pinfunction "BOOT0_60") (pintype "input"))
    )
    (net (code "39") (name "Net-(U1A-NRST)") (class "Default")
      (node (ref "C16") (pin "2") (pinfunction "2_2") (pintype "passive"))
      (node (ref "SW1") (pin "1") (pinfunction "1_1") (pintype "passive"))
      (node (ref "SW1") (pin "3") (pinfunction "3_3") (pintype "passive"))
      (node (ref "U1") (pin "7") (pinfunction "NRST_7") (pintype "bidirectional"))
    )
    (net (code "40") (name "Net-(U1A-PB0)") (class "Default")
      (node (ref "R3") (pin "1") (pinfunction "1_1") (pintype "passive"))
      (node (ref "R4") (pin "2") (pinfunction "2_2") (pintype "passive"))
      (node (ref "U1") (pin "26") (pinfunction "PB0_26") (pintype "bidirectional"))
    )
    (net (code "41") (name "Net-(U1A-PD0-OSC_IN)") (class "Default")
      (node (ref "C12") (pin "1") (pinfunction "1_1") (pintype "passive"))
      (node (ref "U1") (pin "5") (pinfunction "PD0-OSC_IN_5") (pintype "bidirectional"))
      (node (ref "X1") (pin "3") (pinfunction "X2_3") (pintype "passive"))
    )
    (net (code "42") (name "Net-(U1A-PD1-OSC_OUT)") (class "Default")
      (node (ref "C11") (pin "1") (pinfunction "1_1") (pintype "passive"))
      (node (ref "U1") (pin "6") (pinfunction "PD1-OSC_OUT_6") (pintype "bidirectional"))
      (node (ref "X1") (pin "1") (pinfunction "X1_1") (pintype "passive"))
    )
    (net (code "43") (name "Net-(U2-CPH)") (class "Default")
      (node (ref "C6") (pin "2") (pinfunction "2_2") (pintype "passive"))
      (node (ref "U2") (pin "22") (pinfunction "CPH_22") (pintype "power_in"))
    )
    (net (code "44") (name "Net-(U2-CPL)") (class "Default")
      (node (ref "C6") (pin "1") (pinfunction "1_1") (pintype "passive"))
      (node (ref "U2") (pin "23") (pinfunction "CPL_23") (pintype "power_in"))
    )
    (net (code "45") (name "Net-(U2-DVDD)") (class "Default")
      (node (ref "C5") (pin "1") (pinfunction "1_1") (pintype "passive"))
      (node (ref "U2") (pin "1") (pinfunction "DVDD_1") (pintype "power_in"))
    )
    (net (code "46") (name "Net-(U2-VCP)") (class "Default")
      (node (ref "C7") (pin "1") (pinfunction "1_1") (pintype "passive"))
      (node (ref "U2") (pin "21") (pinfunction "VCP_21") (pintype "power_in"))
    )
    (net (code "47") (name "Net-(U3-CPH)") (class "Default")
      (node (ref "C14") (pin "2") (pinfunction "2_2") (pintype "passive"))
      (node (ref "U3") (pin "22") (pinfunction "CPH_22") (pintype "power_in"))
    )
    (net (code "48") (name "Net-(U3-CPL)") (class "Default")
      (node (ref "C14") (pin "1") (pinfunction "1_1") (pintype "passive"))
      (node (ref "U3") (pin "23") (pinfunction "CPL_23") (pintype "power_in"))
    )
    (net (code "49") (name "Net-(U3-DVDD)") (class "Default")
      (node (ref "C13") (pin "1") (pinfunction "1_1") (pintype "passive"))
      (node (ref "U3") (pin "1") (pinfunction "DVDD_1") (pintype "power_in"))
    )
    (net (code "50") (name "Net-(U3-VCP)") (class "Default")
      (node (ref "C15") (pin "1") (pinfunction "1_1") (pintype "passive"))
      (node (ref "U3") (pin "21") (pinfunction "VCP_21") (pintype "power_in"))
    )
    (net (code "51") (name "Net-(U4-CANH)") (class "Default")
      (node (ref "J6") (pin "3") (pinfunction "3_3") (pintype "passive"))
      (node (ref "U4") (pin "7") (pinfunction "CANH_7") (pintype "bidirectional"))
    )
    (net (code "52") (name "Net-(U4-CANL)") (class "Default")
      (node (ref "J6") (pin "2") (pinfunction "2_2") (pintype "passive"))
      (node (ref "U4") (pin "6") (pinfunction "CANL_6") (pintype "bidirectional"))
    )
    (net (code "53") (name "VM") (class "Default")
      (node (ref "C1") (pin "2") (pinfunction "A_2") (pintype "passive"))
      (node (ref "C10") (pin "1") (pinfunction "1_1") (pintype "passive"))
      (node (ref "C15") (pin "2") (pinfunction "2_2") (pintype "passive"))
      (node (ref "C18") (pin "1") (pinfunction "1_1") (pintype "passive"))
      (node (ref "C2") (pin "2") (pinfunction "A_2") (pintype "passive"))
      (node (ref "C20") (pin "1") (pinfunction "1_1") (pintype "passive"))
      (node (ref "C3") (pin "2") (pinfunction "A_2") (pintype "passive"))
      (node (ref "C4") (pin "2") (pinfunction "A_2") (pintype "passive"))
      (node (ref "C7") (pin "2") (pinfunction "2_2") (pintype "passive"))
      (node (ref "C8") (pin "1") (pinfunction "1_1") (pintype "passive"))
      (node (ref "D1") (pin "1") (pinfunction "C_1") (pintype "passive"))
      (node (ref "F1") (pin "2") (pinfunction "2_2") (pintype "passive"))
      (node (ref "U2") (pin "13") (pinfunction "VM_13") (pintype "power_in"))
      (node (ref "U2") (pin "20") (pinfunction "VM_20") (pintype "power_in"))
      (node (ref "U3") (pin "13") (pinfunction "VM_13") (pintype "power_in"))
      (node (ref "U3") (pin "20") (pinfunction "VM_20") (pintype "power_in"))
    )
    (net (code "54") (name "unconnected-(U1A-PA0-WKUP-Pad14)") (class "Default")
      (node (ref "U1") (pin "14") (pinfunction "PA0-WKUP_14") (pintype "bidirectional"))
    )
    (net (code "55") (name "unconnected-(U1A-PA1-Pad15)") (class "Default")
      (node (ref "U1") (pin "15") (pinfunction "PA1_15") (pintype "bidirectional"))
    )
    (net (code "56") (name "unconnected-(U1A-PA2-Pad16)") (class "Default")
      (node (ref "U1") (pin "16") (pinfunction "PA2_16") (pintype "bidirectional"))
    )
    (net (code "57") (name "unconnected-(U1A-PA4-Pad20)") (class "Default")
      (node (ref "U1") (pin "20") (pinfunction "PA4_20") (pintype "bidirectional"))
    )
    (net (code "58") (name "unconnected-(U1A-PA10-Pad43)") (class "Default")
      (node (ref "U1") (pin "43") (pinfunction "PA10_43") (pintype "bidirectional"))
    )
    (net (code "59") (name "unconnected-(U1A-PB2-Pad28)") (class "Default")
      (node (ref "U1") (pin "28") (pinfunction "PB2_28") (pintype "bidirectional"))
    )
    (net (code "60") (name "unconnected-(U1A-PB3-Pad55)") (class "Default")
      (node (ref "U1") (pin "55") (pinfunction "PB3_55") (pintype "bidirectional"))
    )
    (net (code "61") (name "unconnected-(U1A-PB8-Pad61)") (class "Default")
      (node (ref "U1") (pin "61") (pinfunction "PB8_61") (pintype "bidirectional"))
    )
    (net (code "62") (name "unconnected-(U1A-PB9-Pad62)") (class "Default")
      (node (ref "U1") (pin "62") (pinfunction "PB9_62") (pintype "bidirectional"))
    )
    (net (code "63") (name "unconnected-(U1A-PB14-Pad35)") (class "Default")
      (node (ref "U1") (pin "35") (pinfunction "PB14_35") (pintype "bidirectional"))
    )
    (net (code "64") (name "unconnected-(U1A-PC0-Pad8)") (class "Default")
      (node (ref "U1") (pin "8") (pinfunction "PC0_8") (pintype "bidirectional"))
    )
    (net (code "65") (name "unconnected-(U1A-PC1-Pad9)") (class "Default")
      (node (ref "U1") (pin "9") (pinfunction "PC1_9") (pintype "bidirectional"))
    )
    (net (code "66") (name "unconnected-(U1A-PC2-Pad10)") (class "Default")
      (node (ref "U1") (pin "10") (pinfunction "PC2_10") (pintype "bidirectional"))
    )
    (net (code "67") (name "unconnected-(U1A-PC3-Pad11)") (class "Default")
      (node (ref "U1") (pin "11") (pinfunction "PC3_11") (pintype "bidirectional"))
    )
    (net (code "68") (name "unconnected-(U1A-PC4-Pad24)") (class "Default")
      (node (ref "U1") (pin "24") (pinfunction "PC4_24") (pintype "bidirectional"))
    )
    (net (code "69") (name "unconnected-(U1A-PC8-Pad39)") (class "Default")
      (node (ref "U1") (pin "39") (pinfunction "PC8_39") (pintype "bidirectional"))
    )
    (net (code "70") (name "unconnected-(U1A-PC9-Pad40)") (class "Default")
      (node (ref "U1") (pin "40") (pinfunction "PC9_40") (pintype "bidirectional"))
    )
    (net (code "71") (name "unconnected-(U1A-PC11-Pad52)") (class "Default")
      (node (ref "U1") (pin "52") (pinfunction "PC11_52") (pintype "bidirectional"))
    )
    (net (code "72") (name "unconnected-(U1A-PC12-Pad53)") (class "Default")
      (node (ref "U1") (pin "53") (pinfunction "PC12_53") (pintype "bidirectional"))
    )
    (net (code "73") (name "unconnected-(U1A-PC13-TAMPER-RTC-Pad2)") (class "Default")
      (node (ref "U1") (pin "2") (pinfunction "PC13-TAMPER-RTC_2") (pintype "bidirectional"))
    )
    (net (code "74") (name "unconnected-(U1A-PC14-OSC32_IN-Pad3)") (class "Default")
      (node (ref "U1") (pin "3") (pinfunction "PC14-OSC32_IN_3") (pintype "bidirectional"))
    )
    (net (code "75") (name "unconnected-(U1A-PC15-OSC32_OUT-Pad4)") (class "Default")
      (node (ref "U1") (pin "4") (pinfunction "PC15-OSC32_OUT_4") (pintype "bidirectional"))
    )
    (net (code "76") (name "unconnected-(U1A-PD2-Pad54)") (class "Default")
      (node (ref "U1") (pin "54") (pinfunction "PD2_54") (pintype "bidirectional"))
    )
    (net (code "77") (name "unconnected-(U4-VREF-Pad5)") (class "Default")
      (node (ref "U4") (pin "5") (pinfunction "VREF_5") (pintype "output+no_connect"))
    )
  )
)
